# Buttons.net
KiCad netlist of a schematic drawn in Altium Designer
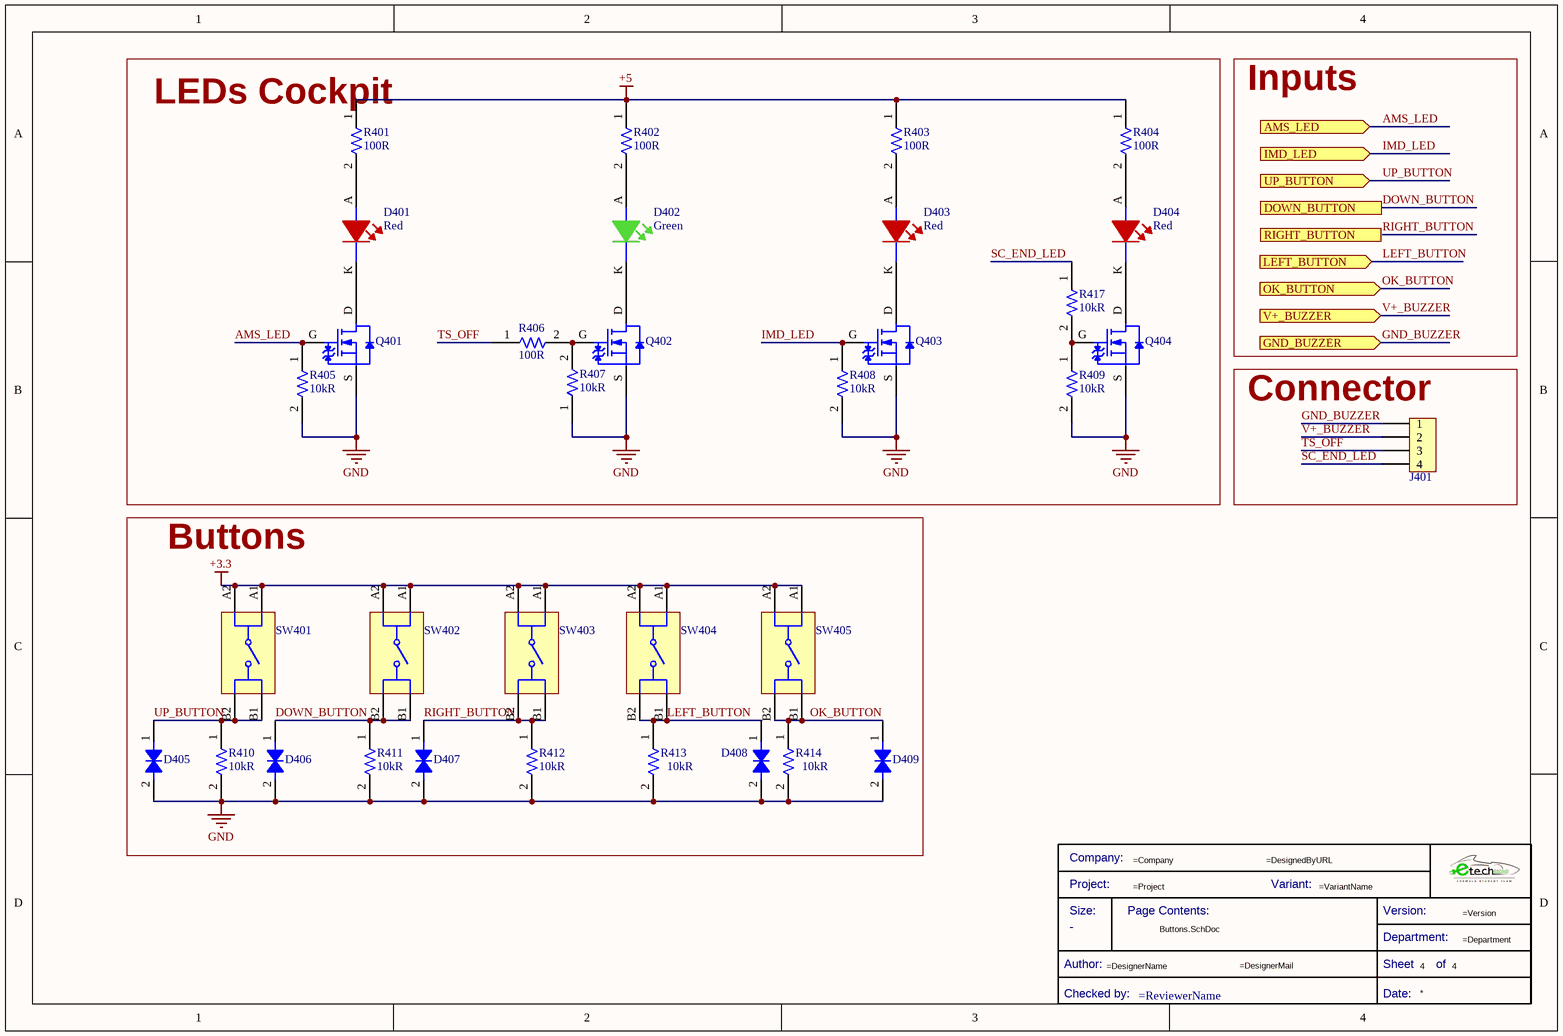
[diagram p0: Buttons.SchDoc]

(export (version "E")
  (design (tool "Eeschema 10.0.6"))
  (components
    (comp (ref "*")
      (value "Title Block_template")
      (description "Standard Title Block")
      (fields
        (field (name "SIZE") "-")
        (field (name ".CREATOR") "GP")
        (field (name ".PCBCHECK") "GP")
        (field (name ".SCHCHECK") "GP")
      )
      (libsource (lib "e-Tech_Racing") (part "Title Block_template"))
    )
    (comp (ref "D401")
      (value "150080RS75000")
      (footprint "LED-THT/WE/D3.9H10.5")
      (description "0805(H=0.8mm) 红色 高亮 λD=625nm VF=2V IF=30mA PD=72mW")
      (fields (field (name "COLOR") "Red") (field (name ".CREATOR") "DR"))
      (libsource (lib "Semiconductor") (part "LEDRS-THT"))
    )
    (comp (ref "D402")
      (value "150080GS75000")
      (footprint "LED-THT/WE/D3.9H10.5")
      (description "Led, Green, 520 Nm, 3.2 V, 30 Ma, 450 Mcd Rohs Compliant: Yes")
      (fields (field (name "COLOR") "Green") (field (name ".CREATOR") "GP"))
      (libsource (lib "Semiconductor") (part "LEDGS-THT"))
    )
    (comp (ref "D403")
      (value "150080RS75000")
      (footprint "LED-THT/WE/D3.9H10.5")
      (description "0805(H=0.8mm) 红色 高亮 λD=625nm VF=2V IF=30mA PD=72mW")
      (fields (field (name "COLOR") "Red") (field (name ".CREATOR") "DR"))
      (libsource (lib "Semiconductor") (part "LEDRS-THT"))
    )
    (comp (ref "D404")
      (value "150080RS75000")
      (footprint "LED-THT/WE/D3.9H10.5")
      (description "0805(H=0.8mm) 红色 高亮 λD=625nm VF=2V IF=30mA PD=72mW")
      (fields (field (name "COLOR") "Red") (field (name ".CREATOR") "DR"))
      (libsource (lib "Semiconductor") (part "LEDRS-THT"))
    )
    (comp (ref "D405")
      (value "824501600")
      (footprint "DTVS-DO-214AC")
      (description "TVS diode [Würth Elektronik] 824501600 TVS diode")
      (fields (field (name "MANUFACTURER") "Wurth Electronics") (field (name ".CREATOR") "DO"))
      (libsource (lib "Filter components") (part "DTVS-6V-DO-214AC"))
    )
    (comp (ref "D406")
      (value "824501600")
      (footprint "DTVS-DO-214AC")
      (description "TVS diode [Würth Elektronik] 824501600 TVS diode")
      (fields (field (name "MANUFACTURER") "Wurth Electronics") (field (name ".CREATOR") "DO"))
      (libsource (lib "Filter components") (part "DTVS-6V-DO-214AC"))
    )
    (comp (ref "D407")
      (value "824501600")
      (footprint "DTVS-DO-214AC")
      (description "TVS diode [Würth Elektronik] 824501600 TVS diode")
      (fields (field (name "MANUFACTURER") "Wurth Electronics") (field (name ".CREATOR") "DO"))
      (libsource (lib "Filter components") (part "DTVS-6V-DO-214AC"))
    )
    (comp (ref "D408")
      (value "824501600")
      (footprint "DTVS-DO-214AC")
      (description "TVS diode [Würth Elektronik] 824501600 TVS diode")
      (fields (field (name "MANUFACTURER") "Wurth Electronics") (field (name ".CREATOR") "DO"))
      (libsource (lib "Filter components") (part "DTVS-6V-DO-214AC"))
    )
    (comp (ref "D409")
      (value "824501600")
      (footprint "DTVS-DO-214AC")
      (description "TVS diode [Würth Elektronik] 824501600 TVS diode")
      (fields (field (name "MANUFACTURER") "Wurth Electronics") (field (name ".CREATOR") "DO"))
      (libsource (lib "Filter components") (part "DTVS-6V-DO-214AC"))
    )
    (comp (ref "J401")
      (value "436500400")
      (footprint "J_MicroFit_1x4")
      (description "Connector Wire to Board Header 4 Position 3mm Solder Right Angle Thru-Hole Tray")
      (libsource (lib "Electromechanical") (part "J_MicroFit_1x4"))
    )
    (comp (ref "Q401")
      (value "SQ2318BES-T1_GE3")
      (footprint "TRT-NCH-3/35-CPH")
      (description "Automotive N-channel 40 V (d-s) 175C Mosfet SOT-23")
      (fields (field (name ".CREATOR") "DO"))
      (libsource (lib "Semiconductor") (part "TRT-NCH-8/40-SQ"))
    )
    (comp (ref "Q402")
      (value "SQ2318BES-T1_GE3")
      (footprint "TRT-NCH-3/35-CPH")
      (description "Automotive N-channel 40 V (d-s) 175C Mosfet SOT-23")
      (fields (field (name ".CREATOR") "DO"))
      (libsource (lib "Semiconductor") (part "TRT-NCH-8/40-SQ"))
    )
    (comp (ref "Q403")
      (value "SQ2318BES-T1_GE3")
      (footprint "TRT-NCH-3/35-CPH")
      (description "Automotive N-channel 40 V (d-s) 175C Mosfet SOT-23")
      (fields (field (name ".CREATOR") "DO"))
      (libsource (lib "Semiconductor") (part "TRT-NCH-8/40-SQ"))
    )
    (comp (ref "Q404")
      (value "SQ2318BES-T1_GE3")
      (footprint "TRT-NCH-3/35-CPH")
      (description "Automotive N-channel 40 V (d-s) 175C Mosfet SOT-23")
      (fields (field (name ".CREATOR") "DO"))
      (libsource (lib "Semiconductor") (part "TRT-NCH-8/40-SQ"))
    )
    (comp (ref "R401")
      (value "CR0805-FX-1000ELF")
      (footprint "R0805FTK")
      (description "Res Thick Film 0805 100 Ohm 1% 1/8W ±100ppm/°C Molded SMD SMD Paper Tape on Plastic Reel")
      (fields
        (field (name "TOLERANCE") "1%")
        (field (name "RESISTANCE") "100R")
        (field (name ".CREATOR") "DR")
      )
      (libsource (lib "Passives") (part "R100-0805FTK"))
    )
    (comp (ref "R402")
      (value "CR0805-FX-1000ELF")
      (footprint "R0805FTK")
      (description "Res Thick Film 0805 100 Ohm 1% 1/8W ±100ppm/°C Molded SMD SMD Paper Tape on Plastic Reel")
      (fields
        (field (name "TOLERANCE") "1%")
        (field (name "RESISTANCE") "100R")
        (field (name ".CREATOR") "DR")
      )
      (libsource (lib "Passives") (part "R100-0805FTK"))
    )
    (comp (ref "R403")
      (value "CR0805-FX-1000ELF")
      (footprint "R0805FTK")
      (description "Res Thick Film 0805 100 Ohm 1% 1/8W ±100ppm/°C Molded SMD SMD Paper Tape on Plastic Reel")
      (fields
        (field (name "TOLERANCE") "1%")
        (field (name "RESISTANCE") "100R")
        (field (name ".CREATOR") "DR")
      )
      (libsource (lib "Passives") (part "R100-0805FTK"))
    )
    (comp (ref "R404")
      (value "CR0805-FX-1000ELF")
      (footprint "R0805FTK")
      (description "Res Thick Film 0805 100 Ohm 1% 1/8W ±100ppm/°C Molded SMD SMD Paper Tape on Plastic Reel")
      (fields
        (field (name "TOLERANCE") "1%")
        (field (name "RESISTANCE") "100R")
        (field (name ".CREATOR") "DR")
      )
      (libsource (lib "Passives") (part "R100-0805FTK"))
    )
    (comp (ref "R405")
      (value "CR0805-JW-103ELF")
      (footprint "R0805FTK")
      (fields
        (field (name "TOLERANCE") "5%")
        (field (name "RESISTANCE") "10kR")
        (field (name ".CREATOR") "DR")
      )
      (libsource (lib "Passives") (part "R10k-0805FTK"))
    )
    (comp (ref "R406")
      (value "CR0805-FX-1000ELF")
      (footprint "R0805FTK")
      (description "Res Thick Film 0805 100 Ohm 1% 1/8W ±100ppm/°C Molded SMD SMD Paper Tape on Plastic Reel")
      (fields
        (field (name "TOLERANCE") "1%")
        (field (name "RESISTANCE") "100R")
        (field (name ".CREATOR") "DR")
      )
      (libsource (lib "Passives") (part "R100-0805FTK"))
    )
    (comp (ref "R407")
      (value "CR0805-JW-103ELF")
      (footprint "R0805FTK")
      (fields
        (field (name "TOLERANCE") "5%")
        (field (name "RESISTANCE") "10kR")
        (field (name ".CREATOR") "DR")
      )
      (libsource (lib "Passives") (part "R10k-0805FTK"))
    )
    (comp (ref "R408")
      (value "CR0805-JW-103ELF")
      (footprint "R0805FTK")
      (fields
        (field (name "TOLERANCE") "5%")
        (field (name "RESISTANCE") "10kR")
        (field (name ".CREATOR") "DR")
      )
      (libsource (lib "Passives") (part "R10k-0805FTK"))
    )
    (comp (ref "R409")
      (value "CR0805-JW-103ELF")
      (footprint "R0805FTK")
      (fields
        (field (name "TOLERANCE") "5%")
        (field (name "RESISTANCE") "10kR")
        (field (name ".CREATOR") "DR")
      )
      (libsource (lib "Passives") (part "R10k-0805FTK"))
    )
    (comp (ref "R410")
      (value "CR0805-JW-103ELF")
      (footprint "R0805FTK")
      (fields
        (field (name "TOLERANCE") "5%")
        (field (name "RESISTANCE") "10kR")
        (field (name ".CREATOR") "DR")
      )
      (libsource (lib "Passives") (part "R10k-0805FTK"))
    )
    (comp (ref "R411")
      (value "CR0805-JW-103ELF")
      (footprint "R0805FTK")
      (fields
        (field (name "TOLERANCE") "5%")
        (field (name "RESISTANCE") "10kR")
        (field (name ".CREATOR") "DR")
      )
      (libsource (lib "Passives") (part "R10k-0805FTK"))
    )
    (comp (ref "R412")
      (value "CR0805-JW-103ELF")
      (footprint "R0805FTK")
      (fields
        (field (name "TOLERANCE") "5%")
        (field (name "RESISTANCE") "10kR")
        (field (name ".CREATOR") "DR")
      )
      (libsource (lib "Passives") (part "R10k-0805FTK"))
    )
    (comp (ref "R413")
      (value "CR0805-JW-103ELF")
      (footprint "R0805FTK")
      (fields
        (field (name "TOLERANCE") "5%")
        (field (name "RESISTANCE") "10kR")
        (field (name ".CREATOR") "DR")
      )
      (libsource (lib "Passives") (part "R10k-0805FTK"))
    )
    (comp (ref "R414")
      (value "CR0805-JW-103ELF")
      (footprint "R0805FTK")
      (fields
        (field (name "TOLERANCE") "5%")
        (field (name "RESISTANCE") "10kR")
        (field (name ".CREATOR") "DR")
      )
      (libsource (lib "Passives") (part "R10k-0805FTK"))
    )
    (comp (ref "R417")
      (value "CR0805-JW-104ELF")
      (footprint "R0805FTK")
      (fields
        (field (name "TOLERANCE") "5%")
        (field (name "RESISTANCE") "10kR")
        (field (name ".CREATOR") "DR")
      )
      (libsource (lib "Passives") (part "R10k-0805FTK"))
    )
    (comp (ref "SW401")
      (value "430456073736")
      (footprint "SWITCH_12x12/4304x60737x6")
      (description "WS-TATV THT Washable Tact Switch 12x12mm, SPST-NO, 12VDC, 50mA, 360g")
      (libsource (lib "Electromechanical") (part "Switch_THT_NO/430456073736"))
    )
    (comp (ref "SW402")
      (value "430456073736")
      (footprint "SWITCH_12x12/4304x60737x6")
      (description "WS-TATV THT Washable Tact Switch 12x12mm, SPST-NO, 12VDC, 50mA, 360g")
      (libsource (lib "Electromechanical") (part "Switch_THT_NO/430456073736"))
    )
    (comp (ref "SW403")
      (value "430456073736")
      (footprint "SWITCH_12x12/4304x60737x6")
      (description "WS-TATV THT Washable Tact Switch 12x12mm, SPST-NO, 12VDC, 50mA, 360g")
      (libsource (lib "Electromechanical") (part "Switch_THT_NO/430456073736"))
    )
    (comp (ref "SW404")
      (value "430456073736")
      (footprint "SWITCH_12x12/4304x60737x6")
      (description "WS-TATV THT Washable Tact Switch 12x12mm, SPST-NO, 12VDC, 50mA, 360g")
      (libsource (lib "Electromechanical") (part "Switch_THT_NO/430456073736"))
    )
    (comp (ref "SW405")
      (value "430456073736")
      (footprint "SWITCH_12x12/4304x60737x6")
      (description "WS-TATV THT Washable Tact Switch 12x12mm, SPST-NO, 12VDC, 50mA, 360g")
      (libsource (lib "Electromechanical") (part "Switch_THT_NO/430456073736"))
    )
  )
  (nets
    (net (code "1") (name "+3.3") (class "Default")
      (node (ref "SW401") (pin "A1") (pinfunction "A1_A1") (pintype "passive"))
      (node (ref "SW401") (pin "A2") (pinfunction "A2_A2") (pintype "passive"))
      (node (ref "SW402") (pin "A1") (pinfunction "A1_A1") (pintype "passive"))
      (node (ref "SW402") (pin "A2") (pinfunction "A2_A2") (pintype "passive"))
      (node (ref "SW403") (pin "A1") (pinfunction "A1_A1") (pintype "passive"))
      (node (ref "SW403") (pin "A2") (pinfunction "A2_A2") (pintype "passive"))
      (node (ref "SW404") (pin "A1") (pinfunction "A1_A1") (pintype "passive"))
      (node (ref "SW404") (pin "A2") (pinfunction "A2_A2") (pintype "passive"))
      (node (ref "SW405") (pin "A1") (pinfunction "A1_A1") (pintype "passive"))
      (node (ref "SW405") (pin "A2") (pinfunction "A2_A2") (pintype "passive"))
    )
    (net (code "2") (name "+5") (class "Default")
      (node (ref "R401") (pin "1") (pinfunction "1_1") (pintype "passive"))
      (node (ref "R402") (pin "1") (pinfunction "1_1") (pintype "passive"))
      (node (ref "R403") (pin "1") (pinfunction "1_1") (pintype "passive"))
      (node (ref "R404") (pin "1") (pinfunction "1_1") (pintype "passive"))
    )
    (net (code "3") (name "/AMS_LED") (class "Default")
      (node (ref "Q401") (pin "G") (pinfunction "G_G") (pintype "passive"))
      (node (ref "R405") (pin "1") (pinfunction "1_1") (pintype "passive"))
    )
    (net (code "4") (name "/DOWN_BUTTON") (class "Default")
      (node (ref "D406") (pin "1") (pinfunction "1_1") (pintype "passive"))
      (node (ref "R411") (pin "1") (pinfunction "1_1") (pintype "passive"))
      (node (ref "SW402") (pin "B1") (pinfunction "B1_B1") (pintype "passive"))
      (node (ref "SW402") (pin "B2") (pinfunction "B2_B2") (pintype "passive"))
    )
    (net (code "5") (name "/GND_BUZZER") (class "Default")
      (node (ref "J401") (pin "1") (pinfunction "1_1") (pintype "passive"))
    )
    (net (code "6") (name "/IMD_LED") (class "Default")
      (node (ref "Q403") (pin "G") (pinfunction "G_G") (pintype "passive"))
      (node (ref "R408") (pin "1") (pinfunction "1_1") (pintype "passive"))
    )
    (net (code "7") (name "/LEFT_BUTTON") (class "Default")
      (node (ref "D408") (pin "1") (pinfunction "1_1") (pintype "passive"))
      (node (ref "R413") (pin "1") (pinfunction "1_1") (pintype "passive"))
      (node (ref "SW404") (pin "B1") (pinfunction "B1_B1") (pintype "passive"))
      (node (ref "SW404") (pin "B2") (pinfunction "B2_B2") (pintype "passive"))
    )
    (net (code "8") (name "/OK_BUTTON") (class "Default")
      (node (ref "D409") (pin "1") (pinfunction "1_1") (pintype "passive"))
      (node (ref "R414") (pin "1") (pinfunction "1_1") (pintype "passive"))
      (node (ref "SW405") (pin "B1") (pinfunction "B1_B1") (pintype "passive"))
      (node (ref "SW405") (pin "B2") (pinfunction "B2_B2") (pintype "passive"))
    )
    (net (code "9") (name "/RIGHT_BUTTON") (class "Default")
      (node (ref "D407") (pin "1") (pinfunction "1_1") (pintype "passive"))
      (node (ref "R412") (pin "1") (pinfunction "1_1") (pintype "passive"))
      (node (ref "SW403") (pin "B1") (pinfunction "B1_B1") (pintype "passive"))
      (node (ref "SW403") (pin "B2") (pinfunction "B2_B2") (pintype "passive"))
    )
    (net (code "10") (name "/SC_END_LED") (class "Default")
      (node (ref "J401") (pin "4") (pinfunction "4_4") (pintype "passive"))
      (node (ref "R417") (pin "1") (pinfunction "1_1") (pintype "passive"))
    )
    (net (code "11") (name "/TS_OFF") (class "Default")
      (node (ref "J401") (pin "3") (pinfunction "3_3") (pintype "passive"))
      (node (ref "R406") (pin "1") (pinfunction "1_1") (pintype "passive"))
    )
    (net (code "12") (name "/UP_BUTTON") (class "Default")
      (node (ref "D405") (pin "1") (pinfunction "1_1") (pintype "passive"))
      (node (ref "R410") (pin "1") (pinfunction "1_1") (pintype "passive"))
      (node (ref "SW401") (pin "B1") (pinfunction "B1_B1") (pintype "passive"))
      (node (ref "SW401") (pin "B2") (pinfunction "B2_B2") (pintype "passive"))
    )
    (net (code "13") (name "/V+_BUZZER") (class "Default")
      (node (ref "J401") (pin "2") (pinfunction "2_2") (pintype "passive"))
    )
    (net (code "14") (name "GND") (class "Default")
      (node (ref "D405") (pin "2") (pinfunction "2_2") (pintype "passive"))
      (node (ref "D406") (pin "2") (pinfunction "2_2") (pintype "passive"))
      (node (ref "D407") (pin "2") (pinfunction "2_2") (pintype "passive"))
      (node (ref "D408") (pin "2") (pinfunction "2_2") (pintype "passive"))
      (node (ref "D409") (pin "2") (pinfunction "2_2") (pintype "passive"))
      (node (ref "Q401") (pin "S") (pinfunction "S_S") (pintype "passive"))
      (node (ref "Q402") (pin "S") (pinfunction "S_S") (pintype "passive"))
      (node (ref "Q403") (pin "S") (pinfunction "S_S") (pintype "passive"))
      (node (ref "Q404") (pin "S") (pinfunction "S_S") (pintype "passive"))
      (node (ref "R405") (pin "2") (pinfunction "2_2") (pintype "passive"))
      (node (ref "R407") (pin "1") (pinfunction "1_1") (pintype "passive"))
      (node (ref "R408") (pin "2") (pinfunction "2_2") (pintype "passive"))
      (node (ref "R409") (pin "2") (pinfunction "2_2") (pintype "passive"))
      (node (ref "R410") (pin "2") (pinfunction "2_2") (pintype "passive"))
      (node (ref "R411") (pin "2") (pinfunction "2_2") (pintype "passive"))
      (node (ref "R412") (pin "2") (pinfunction "2_2") (pintype "passive"))
      (node (ref "R413") (pin "2") (pinfunction "2_2") (pintype "passive"))
      (node (ref "R414") (pin "2") (pinfunction "2_2") (pintype "passive"))
    )
    (net (code "15") (name "Net-(D401-PadA)") (class "Default")
      (node (ref "D401") (pin "A") (pinfunction "A_A") (pintype "passive"))
      (node (ref "R401") (pin "2") (pinfunction "2_2") (pintype "passive"))
    )
    (net (code "16") (name "Net-(D401-PadK)") (class "Default")
      (node (ref "D401") (pin "K") (pinfunction "K_K") (pintype "passive"))
      (node (ref "Q401") (pin "D") (pinfunction "D_D") (pintype "passive"))
    )
    (net (code "17") (name "Net-(D402-PadA)") (class "Default")
      (node (ref "D402") (pin "A") (pinfunction "A_A") (pintype "passive"))
      (node (ref "R402") (pin "2") (pinfunction "2_2") (pintype "passive"))
    )
    (net (code "18") (name "Net-(D402-PadK)") (class "Default")
      (node (ref "D402") (pin "K") (pinfunction "K_K") (pintype "passive"))
      (node (ref "Q402") (pin "D") (pinfunction "D_D") (pintype "passive"))
    )
    (net (code "19") (name "Net-(D403-PadA)") (class "Default")
      (node (ref "D403") (pin "A") (pinfunction "A_A") (pintype "passive"))
      (node (ref "R403") (pin "2") (pinfunction "2_2") (pintype "passive"))
    )
    (net (code "20") (name "Net-(D403-PadK)") (class "Default")
      (node (ref "D403") (pin "K") (pinfunction "K_K") (pintype "passive"))
      (node (ref "Q403") (pin "D") (pinfunction "D_D") (pintype "passive"))
    )
    (net (code "21") (name "Net-(D404-PadA)") (class "Default")
      (node (ref "D404") (pin "A") (pinfunction "A_A") (pintype "passive"))
      (node (ref "R404") (pin "2") (pinfunction "2_2") (pintype "passive"))
    )
    (net (code "22") (name "Net-(D404-PadK)") (class "Default")
      (node (ref "D404") (pin "K") (pinfunction "K_K") (pintype "passive"))
      (node (ref "Q404") (pin "D") (pinfunction "D_D") (pintype "passive"))
    )
    (net (code "23") (name "Net-(Q402-PadG)") (class "Default")
      (node (ref "Q402") (pin "G") (pinfunction "G_G") (pintype "passive"))
      (node (ref "R406") (pin "2") (pinfunction "2_2") (pintype "passive"))
      (node (ref "R407") (pin "2") (pinfunction "2_2") (pintype "passive"))
    )
    (net (code "24") (name "Net-(Q404-PadG)") (class "Default")
      (node (ref "Q404") (pin "G") (pinfunction "G_G") (pintype "passive"))
      (node (ref "R409") (pin "1") (pinfunction "1_1") (pintype "passive"))
      (node (ref "R417") (pin "2") (pinfunction "2_2") (pintype "passive"))
    )
  )
)
